# ioboard.net
KiCad netlist of a schematic drawn in EAGLE
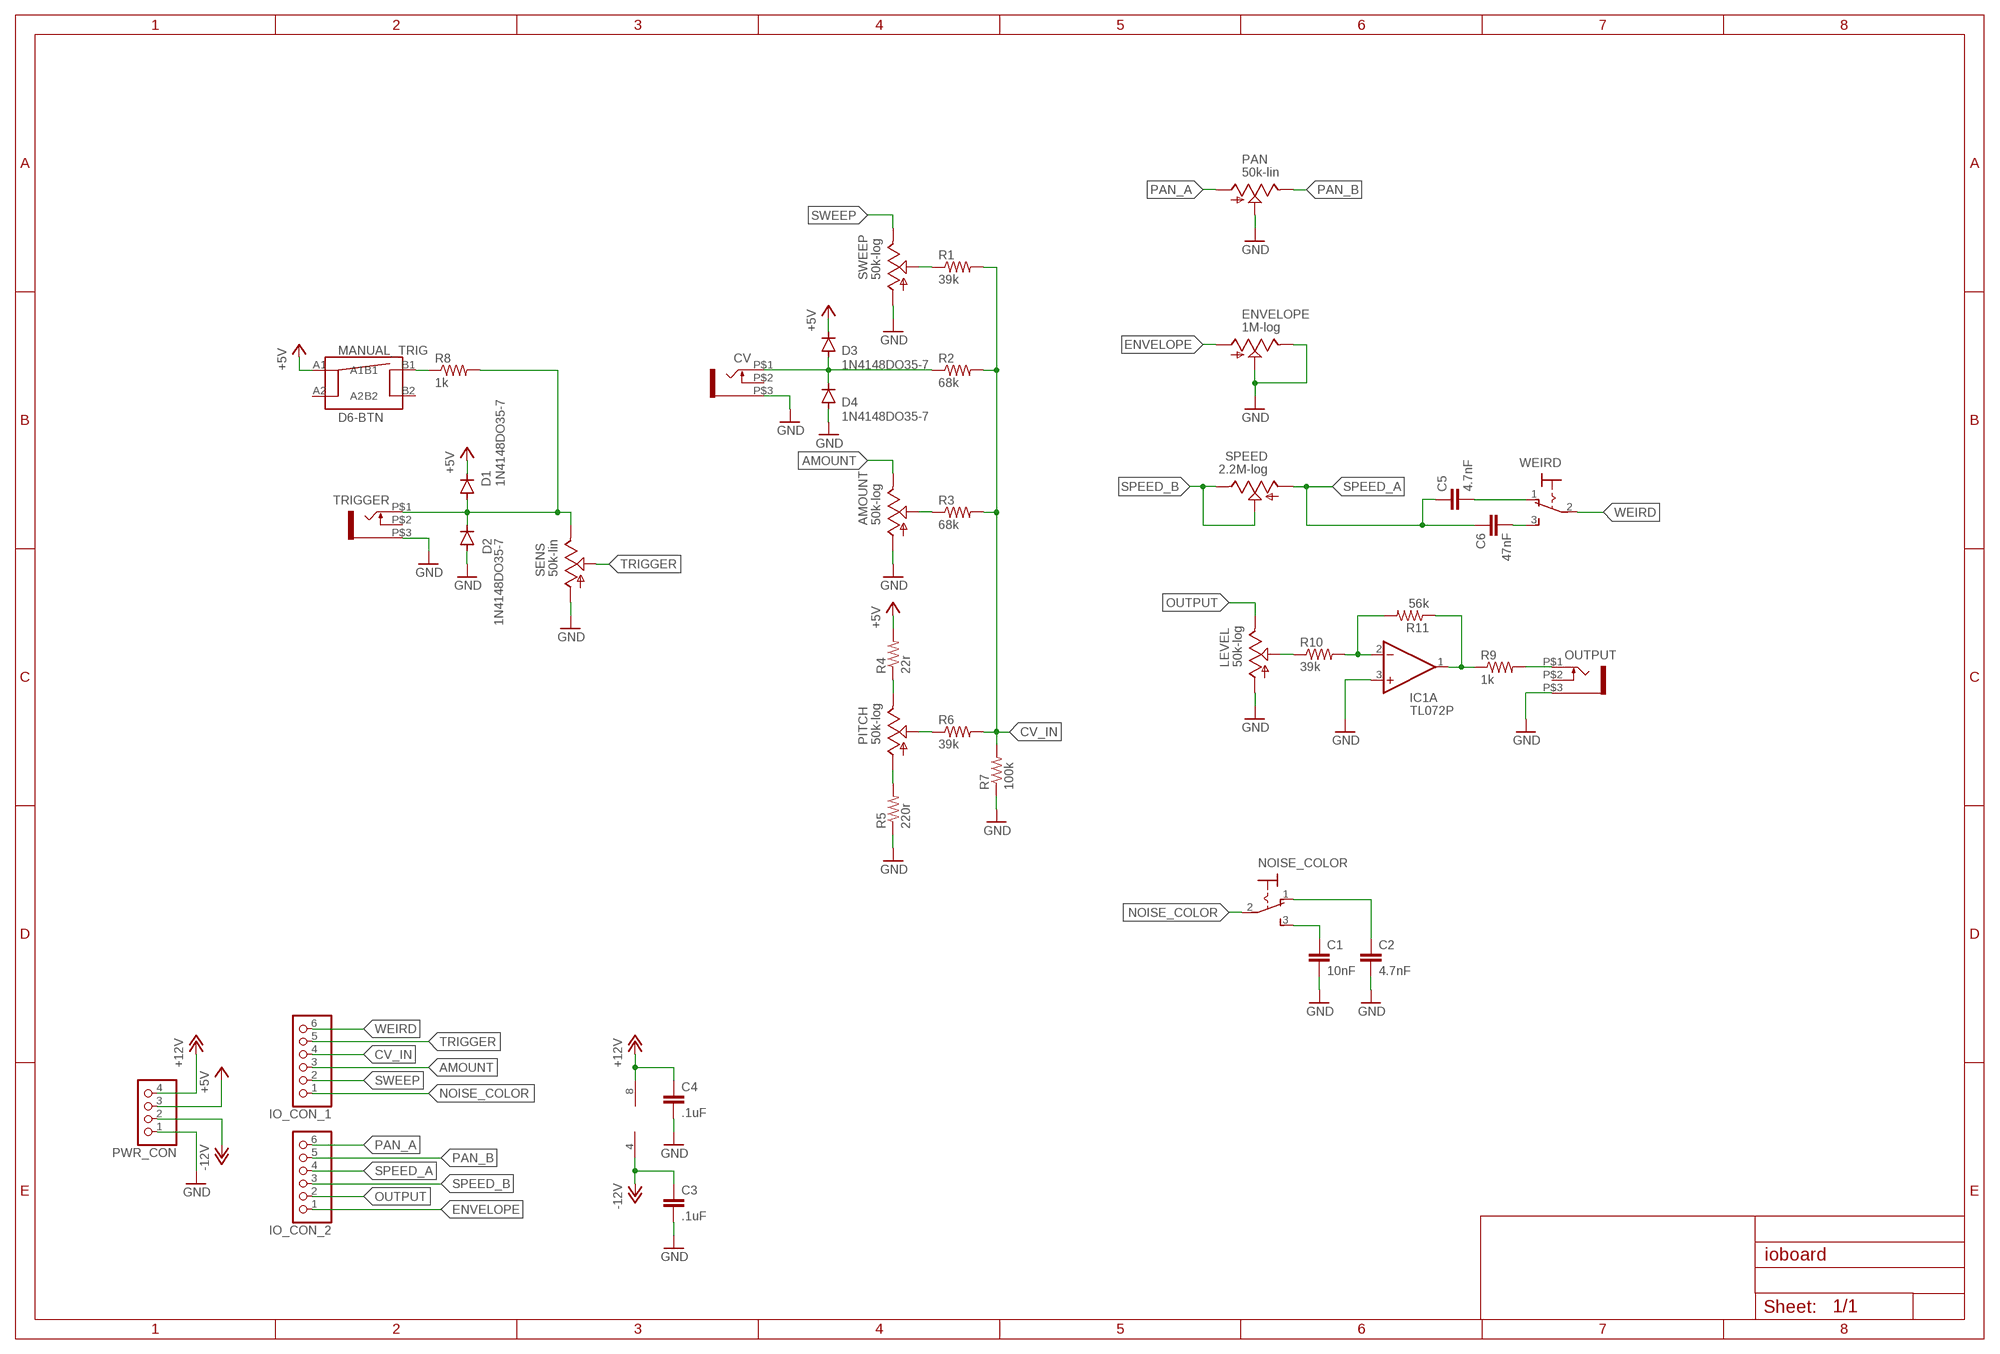
[diagram p0: schematic, sheet 1]

(export (version "E")
  (design (tool "Eeschema 10.0.6"))
  (components
    (comp (ref "AMOUNT")
      (value "50k-log")
      (footprint "eagle-import:EVUF")
      (libsource (lib "eagle-import") (part "ALPHA-9MMA"))
    )
    (comp (ref "C1")
      (value "10nF")
      (footprint "eagle-import:C050-024X044")
      (libsource (lib "eagle-import") (part "C-EU050-024X044"))
    )
    (comp (ref "C2")
      (value "4.7nF")
      (footprint "eagle-import:C050-024X044")
      (libsource (lib "eagle-import") (part "C-EU050-024X044"))
    )
    (comp (ref "C3")
      (value ".1uF")
      (footprint "eagle-import:C050-024X044")
      (libsource (lib "eagle-import") (part "C-EU050-024X044"))
    )
    (comp (ref "C4")
      (value ".1uF")
      (footprint "eagle-import:C050-024X044")
      (libsource (lib "eagle-import") (part "C-EU050-024X044"))
    )
    (comp (ref "C5")
      (value "4.7nF")
      (footprint "eagle-import:C050-024X044")
      (libsource (lib "eagle-import") (part "C-EU050-024X044"))
    )
    (comp (ref "C6")
      (value "47nF")
      (footprint "eagle-import:C050-024X044")
      (libsource (lib "eagle-import") (part "C-EU050-024X044"))
    )
    (comp (ref "CV")
      (value "WQP-PJ301M-12_JACK")
      (footprint "eagle-import:WQP-PJ301M-12_JACK")
      (libsource (lib "eagle-import") (part "WQP-PJ301M-12_JACK"))
    )
    (comp (ref "D1")
      (value "1N4148DO35-7")
      (footprint "eagle-import:DO35-7")
      (libsource (lib "eagle-import") (part "1N4148DO35-7"))
    )
    (comp (ref "D2")
      (value "1N4148DO35-7")
      (footprint "eagle-import:DO35-7")
      (libsource (lib "eagle-import") (part "1N4148DO35-7"))
    )
    (comp (ref "D3")
      (value "1N4148DO35-7")
      (footprint "eagle-import:DO35-7")
      (libsource (lib "eagle-import") (part "1N4148DO35-7"))
    )
    (comp (ref "D4")
      (value "1N4148DO35-7")
      (footprint "eagle-import:DO35-7")
      (libsource (lib "eagle-import") (part "1N4148DO35-7"))
    )
    (comp (ref "ENVELOPE")
      (value "1M-log")
      (footprint "eagle-import:EVUF")
      (libsource (lib "eagle-import") (part "ALPHA-9MMA"))
    )
    (comp (ref "IC1")
      (value "TL072P")
      (footprint "eagle-import:DIL08")
      (libsource (lib "eagle-import") (part "TL072P"))
    )
    (comp (ref "IO_CON_1")
      (value "PINHD-1X6")
      (footprint "eagle-import:1X06")
      (libsource (lib "eagle-import") (part "PINHD-1X6"))
    )
    (comp (ref "IO_CON_2")
      (value "PINHD-1X6")
      (footprint "eagle-import:1X06")
      (libsource (lib "eagle-import") (part "PINHD-1X6"))
    )
    (comp (ref "LEVEL")
      (value "50k-log")
      (footprint "eagle-import:EVUF")
      (libsource (lib "eagle-import") (part "ALPHA-9MMA"))
    )
    (comp (ref "MANUAL_TRIG")
      (value "D6-BTN")
      (footprint "eagle-import:D6-BTN")
      (libsource (lib "eagle-import") (part "D6-BTN"))
    )
    (comp (ref "NOISE_COLOR")
      (value "M9040P")
      (footprint "eagle-import:M9040P")
      (libsource (lib "eagle-import") (part "M9040P"))
    )
    (comp (ref "OUTPUT")
      (value "WQP-PJ301M-12_JACK")
      (footprint "eagle-import:WQP-PJ301M-12_JACK")
      (libsource (lib "eagle-import") (part "WQP-PJ301M-12_JACK"))
    )
    (comp (ref "PAN")
      (value "50k-lin")
      (footprint "eagle-import:EVUF")
      (libsource (lib "eagle-import") (part "ALPHA-9MMA"))
    )
    (comp (ref "PITCH")
      (value "50k-log")
      (footprint "eagle-import:EVUF")
      (libsource (lib "eagle-import") (part "ALPHA-9MMA"))
    )
    (comp (ref "PWR_CON")
      (value "PINHD-1X4")
      (footprint "eagle-import:1X04")
      (libsource (lib "eagle-import") (part "PINHD-1X4"))
    )
    (comp (ref "R1")
      (value "39k")
      (footprint "eagle-import:0207_7")
      (libsource (lib "eagle-import") (part "R-US_0207/7"))
    )
    (comp (ref "R2")
      (value "68k")
      (footprint "eagle-import:0207_7")
      (libsource (lib "eagle-import") (part "R-US_0207/7"))
    )
    (comp (ref "R3")
      (value "68k")
      (footprint "eagle-import:0207_7")
      (libsource (lib "eagle-import") (part "R-US_0207/7"))
    )
    (comp (ref "R4")
      (value "22r")
      (footprint "eagle-import:0207_7")
      (libsource (lib "eagle-import") (part "R-US_0207/7"))
    )
    (comp (ref "R5")
      (value "220r")
      (footprint "eagle-import:0207_7")
      (libsource (lib "eagle-import") (part "R-US_0207/7"))
    )
    (comp (ref "R6")
      (value "39k")
      (footprint "eagle-import:0207_7")
      (libsource (lib "eagle-import") (part "R-US_0207/7"))
    )
    (comp (ref "R7")
      (value "100k")
      (footprint "eagle-import:0207_7")
      (libsource (lib "eagle-import") (part "R-US_0207/7"))
    )
    (comp (ref "R8")
      (value "1k")
      (footprint "eagle-import:0207_7")
      (libsource (lib "eagle-import") (part "R-US_0207/7"))
    )
    (comp (ref "R9")
      (value "1k")
      (footprint "eagle-import:0207_7")
      (libsource (lib "eagle-import") (part "R-US_0207/7"))
    )
    (comp (ref "R10")
      (value "39k")
      (footprint "eagle-import:0207_7")
      (libsource (lib "eagle-import") (part "R-US_0207/7"))
    )
    (comp (ref "R11")
      (value "56k")
      (footprint "eagle-import:0207_7")
      (libsource (lib "eagle-import") (part "R-US_0207/7"))
    )
    (comp (ref "SENS")
      (value "50k-lin")
      (footprint "eagle-import:EVUF")
      (libsource (lib "eagle-import") (part "ALPHA-9MMA"))
    )
    (comp (ref "SPEED")
      (value "2.2M-log")
      (footprint "eagle-import:EVUF")
      (libsource (lib "eagle-import") (part "ALPHA-9MMA"))
    )
    (comp (ref "SWEEP")
      (value "50k-log")
      (footprint "eagle-import:EVUF")
      (libsource (lib "eagle-import") (part "ALPHA-9MMA"))
    )
    (comp (ref "TRIGGER")
      (value "WQP-PJ301M-12_JACK")
      (footprint "eagle-import:WQP-PJ301M-12_JACK")
      (libsource (lib "eagle-import") (part "WQP-PJ301M-12_JACK"))
    )
    (comp (ref "WEIRD")
      (value "M9040P")
      (footprint "eagle-import:M9040P")
      (libsource (lib "eagle-import") (part "M9040P"))
    )
  )
  (nets
    (net (code "1") (name "+5V") (class "Default")
      (node (ref "D1") (pin "C") (pinfunction "C_C") (pintype "passive"))
      (node (ref "D3") (pin "C") (pinfunction "C_C") (pintype "passive"))
      (node (ref "MANUAL_TRIG") (pin "A1") (pinfunction "A1_A1") (pintype "bidirectional"))
      (node (ref "PWR_CON") (pin "3") (pinfunction "3_3") (pintype "passive"))
      (node (ref "R4") (pin "2") (pinfunction "2_2") (pintype "passive"))
    )
    (net (code "2") (name "+12V") (class "Default")
      (node (ref "C4") (pin "1") (pinfunction "1_1") (pintype "passive"))
      (node (ref "IC1") (pin "8") (pinfunction "V+_8") (pintype "power_in"))
      (node (ref "PWR_CON") (pin "4") (pinfunction "4_4") (pintype "passive"))
    )
    (net (code "3") (name "-12V") (class "Default")
      (node (ref "C3") (pin "1") (pinfunction "1_1") (pintype "passive"))
      (node (ref "IC1") (pin "4") (pinfunction "V-_4") (pintype "power_in"))
      (node (ref "PWR_CON") (pin "2") (pinfunction "2_2") (pintype "passive"))
    )
    (net (code "4") (name "AMOUNT") (class "Default")
      (node (ref "AMOUNT") (pin "3") (pinfunction "E_3") (pintype "passive"))
      (node (ref "IO_CON_1") (pin "3") (pinfunction "3_3") (pintype "passive"))
    )
    (net (code "5") (name "CV_IN") (class "Default")
      (node (ref "IO_CON_1") (pin "4") (pinfunction "4_4") (pintype "passive"))
      (node (ref "R1") (pin "2") (pinfunction "2_2") (pintype "passive"))
      (node (ref "R2") (pin "2") (pinfunction "2_2") (pintype "passive"))
      (node (ref "R3") (pin "2") (pinfunction "2_2") (pintype "passive"))
      (node (ref "R6") (pin "2") (pinfunction "2_2") (pintype "passive"))
      (node (ref "R7") (pin "2") (pinfunction "2_2") (pintype "passive"))
    )
    (net (code "6") (name "ENVELOPE") (class "Default")
      (node (ref "ENVELOPE") (pin "1") (pinfunction "A_1") (pintype "passive"))
      (node (ref "IO_CON_2") (pin "1") (pinfunction "1_1") (pintype "passive"))
    )
    (net (code "7") (name "GND") (class "Default")
      (node (ref "AMOUNT") (pin "1") (pinfunction "A_1") (pintype "passive"))
      (node (ref "C1") (pin "2") (pinfunction "2_2") (pintype "passive"))
      (node (ref "C2") (pin "2") (pinfunction "2_2") (pintype "passive"))
      (node (ref "C3") (pin "2") (pinfunction "2_2") (pintype "passive"))
      (node (ref "C4") (pin "2") (pinfunction "2_2") (pintype "passive"))
      (node (ref "CV") (pin "P$3") (pinfunction "1_P$3") (pintype "passive"))
      (node (ref "D2") (pin "A") (pinfunction "A_A") (pintype "passive"))
      (node (ref "D4") (pin "A") (pinfunction "A_A") (pintype "passive"))
      (node (ref "ENVELOPE") (pin "2") (pinfunction "S_2") (pintype "passive"))
      (node (ref "ENVELOPE") (pin "3") (pinfunction "E_3") (pintype "passive"))
      (node (ref "IC1") (pin "3") (pinfunction "+IN_3") (pintype "input"))
      (node (ref "LEVEL") (pin "1") (pinfunction "A_1") (pintype "passive"))
      (node (ref "OUTPUT") (pin "P$3") (pinfunction "1_P$3") (pintype "passive"))
      (node (ref "PAN") (pin "2") (pinfunction "S_2") (pintype "passive"))
      (node (ref "PWR_CON") (pin "1") (pinfunction "1_1") (pintype "passive"))
      (node (ref "R5") (pin "1") (pinfunction "1_1") (pintype "passive"))
      (node (ref "R7") (pin "1") (pinfunction "1_1") (pintype "passive"))
      (node (ref "SENS") (pin "1") (pinfunction "A_1") (pintype "passive"))
      (node (ref "SWEEP") (pin "1") (pinfunction "A_1") (pintype "passive"))
      (node (ref "TRIGGER") (pin "P$3") (pinfunction "1_P$3") (pintype "passive"))
    )
    (net (code "8") (name "NOISE_COLOR") (class "Default")
      (node (ref "IO_CON_1") (pin "1") (pinfunction "1_1") (pintype "passive"))
      (node (ref "NOISE_COLOR") (pin "2") (pinfunction "P_2") (pintype "passive"))
    )
    (net (code "9") (name "Net-(AMOUNT-S)") (class "Default")
      (node (ref "AMOUNT") (pin "2") (pinfunction "S_2") (pintype "passive"))
      (node (ref "R3") (pin "1") (pinfunction "1_1") (pintype "passive"))
    )
    (net (code "10") (name "Net-(CV-2)") (class "Default")
      (node (ref "CV") (pin "P$1") (pinfunction "2_P$1") (pintype "passive"))
      (node (ref "D3") (pin "A") (pinfunction "A_A") (pintype "passive"))
      (node (ref "D4") (pin "C") (pinfunction "C_C") (pintype "passive"))
      (node (ref "R2") (pin "1") (pinfunction "1_1") (pintype "passive"))
    )
    (net (code "11") (name "Net-(IC1A--IN)") (class "Default")
      (node (ref "IC1") (pin "2") (pinfunction "-IN_2") (pintype "input"))
      (node (ref "R10") (pin "2") (pinfunction "2_2") (pintype "passive"))
      (node (ref "R11") (pin "2") (pinfunction "2_2") (pintype "passive"))
    )
    (net (code "12") (name "Net-(IC1A-OUT)") (class "Default")
      (node (ref "IC1") (pin "1") (pinfunction "OUT_1") (pintype "output"))
      (node (ref "R11") (pin "1") (pinfunction "1_1") (pintype "passive"))
      (node (ref "R9") (pin "1") (pinfunction "1_1") (pintype "passive"))
    )
    (net (code "13") (name "Net-(LEVEL-S)") (class "Default")
      (node (ref "LEVEL") (pin "2") (pinfunction "S_2") (pintype "passive"))
      (node (ref "R10") (pin "1") (pinfunction "1_1") (pintype "passive"))
    )
    (net (code "14") (name "Net-(MANUAL_TRIG-PadB1)") (class "Default")
      (node (ref "MANUAL_TRIG") (pin "B1") (pinfunction "B1_B1") (pintype "bidirectional"))
      (node (ref "R8") (pin "1") (pinfunction "1_1") (pintype "passive"))
    )
    (net (code "15") (name "Net-(NOISE_COLOR-O)") (class "Default")
      (node (ref "C2") (pin "1") (pinfunction "1_1") (pintype "passive"))
      (node (ref "NOISE_COLOR") (pin "1") (pinfunction "O_1") (pintype "passive"))
    )
    (net (code "16") (name "Net-(NOISE_COLOR-S)") (class "Default")
      (node (ref "C1") (pin "1") (pinfunction "1_1") (pintype "passive"))
      (node (ref "NOISE_COLOR") (pin "3") (pinfunction "S_3") (pintype "passive"))
    )
    (net (code "17") (name "Net-(OUTPUT-2)") (class "Default")
      (node (ref "OUTPUT") (pin "P$1") (pinfunction "2_P$1") (pintype "passive"))
      (node (ref "R9") (pin "2") (pinfunction "2_2") (pintype "passive"))
    )
    (net (code "18") (name "Net-(PITCH-A)") (class "Default")
      (node (ref "PITCH") (pin "1") (pinfunction "A_1") (pintype "passive"))
      (node (ref "R5") (pin "2") (pinfunction "2_2") (pintype "passive"))
    )
    (net (code "19") (name "Net-(PITCH-E)") (class "Default")
      (node (ref "PITCH") (pin "3") (pinfunction "E_3") (pintype "passive"))
      (node (ref "R4") (pin "1") (pinfunction "1_1") (pintype "passive"))
    )
    (net (code "20") (name "Net-(PITCH-S)") (class "Default")
      (node (ref "PITCH") (pin "2") (pinfunction "S_2") (pintype "passive"))
      (node (ref "R6") (pin "1") (pinfunction "1_1") (pintype "passive"))
    )
    (net (code "21") (name "Net-(SENS-E)") (class "Default")
      (node (ref "D1") (pin "A") (pinfunction "A_A") (pintype "passive"))
      (node (ref "D2") (pin "C") (pinfunction "C_C") (pintype "passive"))
      (node (ref "R8") (pin "2") (pinfunction "2_2") (pintype "passive"))
      (node (ref "SENS") (pin "3") (pinfunction "E_3") (pintype "passive"))
      (node (ref "TRIGGER") (pin "P$1") (pinfunction "2_P$1") (pintype "passive"))
    )
    (net (code "22") (name "Net-(SWEEP-S)") (class "Default")
      (node (ref "R1") (pin "1") (pinfunction "1_1") (pintype "passive"))
      (node (ref "SWEEP") (pin "2") (pinfunction "S_2") (pintype "passive"))
    )
    (net (code "23") (name "Net-(WEIRD-O)") (class "Default")
      (node (ref "C5") (pin "2") (pinfunction "2_2") (pintype "passive"))
      (node (ref "WEIRD") (pin "1") (pinfunction "O_1") (pintype "passive"))
    )
    (net (code "24") (name "Net-(WEIRD-S)") (class "Default")
      (node (ref "C6") (pin "2") (pinfunction "2_2") (pintype "passive"))
      (node (ref "WEIRD") (pin "3") (pinfunction "S_3") (pintype "passive"))
    )
    (net (code "25") (name "OUTPUT") (class "Default")
      (node (ref "IO_CON_2") (pin "2") (pinfunction "2_2") (pintype "passive"))
      (node (ref "LEVEL") (pin "3") (pinfunction "E_3") (pintype "passive"))
    )
    (net (code "26") (name "PAN_A") (class "Default")
      (node (ref "IO_CON_2") (pin "6") (pinfunction "6_6") (pintype "passive"))
      (node (ref "PAN") (pin "1") (pinfunction "A_1") (pintype "passive"))
    )
    (net (code "27") (name "PAN_B") (class "Default")
      (node (ref "IO_CON_2") (pin "5") (pinfunction "5_5") (pintype "passive"))
      (node (ref "PAN") (pin "3") (pinfunction "E_3") (pintype "passive"))
    )
    (net (code "28") (name "SPEED_A") (class "Default")
      (node (ref "C5") (pin "1") (pinfunction "1_1") (pintype "passive"))
      (node (ref "C6") (pin "1") (pinfunction "1_1") (pintype "passive"))
      (node (ref "IO_CON_2") (pin "4") (pinfunction "4_4") (pintype "passive"))
      (node (ref "SPEED") (pin "1") (pinfunction "A_1") (pintype "passive"))
    )
    (net (code "29") (name "SPEED_B") (class "Default")
      (node (ref "IO_CON_2") (pin "3") (pinfunction "3_3") (pintype "passive"))
      (node (ref "SPEED") (pin "2") (pinfunction "S_2") (pintype "passive"))
      (node (ref "SPEED") (pin "3") (pinfunction "E_3") (pintype "passive"))
    )
    (net (code "30") (name "SWEEP") (class "Default")
      (node (ref "IO_CON_1") (pin "2") (pinfunction "2_2") (pintype "passive"))
      (node (ref "SWEEP") (pin "3") (pinfunction "E_3") (pintype "passive"))
    )
    (net (code "31") (name "TRIGGER") (class "Default")
      (node (ref "IO_CON_1") (pin "5") (pinfunction "5_5") (pintype "passive"))
      (node (ref "SENS") (pin "2") (pinfunction "S_2") (pintype "passive"))
    )
    (net (code "32") (name "WEIRD") (class "Default")
      (node (ref "IO_CON_1") (pin "6") (pinfunction "6_6") (pintype "passive"))
      (node (ref "WEIRD") (pin "2") (pinfunction "P_2") (pintype "passive"))
    )
    (net (code "33") (name "unconnected-(CV-3-PadP$2)") (class "Default")
      (node (ref "CV") (pin "P$2") (pinfunction "3_P$2") (pintype "passive"))
    )
    (net (code "34") (name "unconnected-(MANUAL_TRIG-PadA2)") (class "Default")
      (node (ref "MANUAL_TRIG") (pin "A2") (pinfunction "A2_A2") (pintype "bidirectional"))
    )
    (net (code "35") (name "unconnected-(MANUAL_TRIG-PadB2)") (class "Default")
      (node (ref "MANUAL_TRIG") (pin "B2") (pinfunction "B2_B2") (pintype "bidirectional"))
    )
    (net (code "36") (name "unconnected-(OUTPUT-3-PadP$2)") (class "Default")
      (node (ref "OUTPUT") (pin "P$2") (pinfunction "3_P$2") (pintype "passive"))
    )
    (net (code "37") (name "unconnected-(TRIGGER-3-PadP$2)") (class "Default")
      (node (ref "TRIGGER") (pin "P$2") (pinfunction "3_P$2") (pintype "passive"))
    )
  )
)
